# hlk-7688A-kit-v2_2.net
KiCad netlist of a schematic drawn in Altium Designer
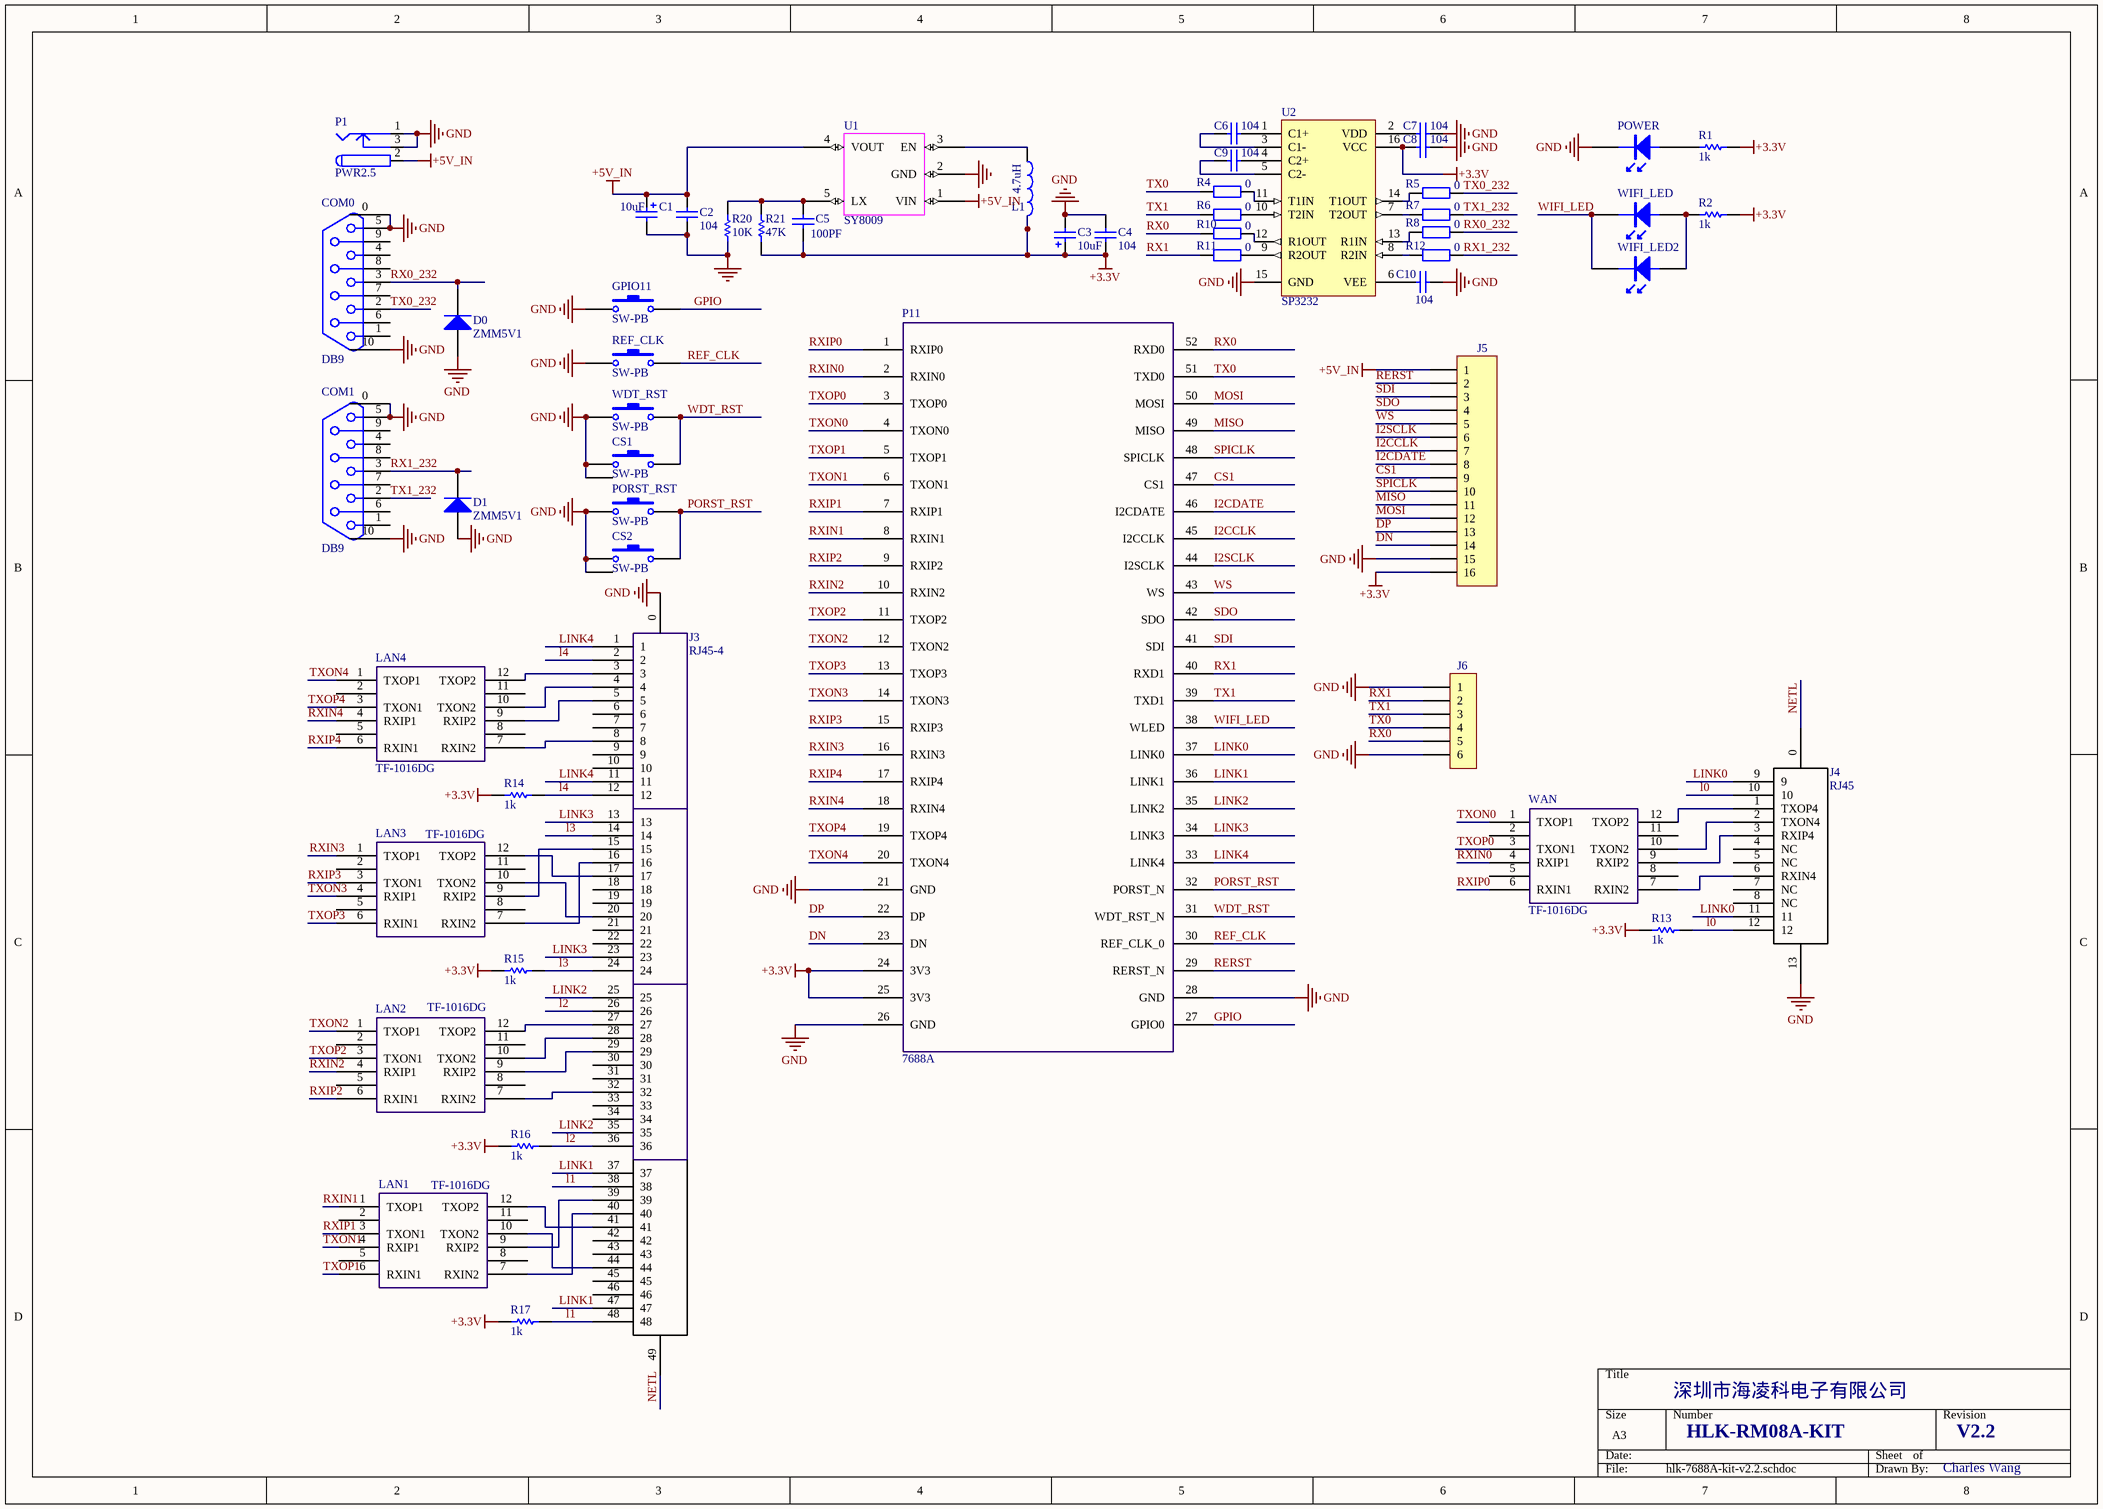
[diagram p0: hlk-7688A-kit-v2.2.schdoc]

(export (version "E")
  (design (tool "Eeschema 10.0.6"))
  (components
    (comp (ref "C1")
      (value "10uF")
      (footprint "0805")
      (description "Polarized Capacitor (Surface Mount)")
      (fields
        (field (name "MANUFACTURER") "Generic Components")
        (field (name "PUBLISHER") "Altium Hobart Technology Centre")
      )
      (libsource (lib "*") (part "Cap Pol3"))
    )
    (comp (ref "C2")
      (value "104")
      (footprint "0603L")
      (description "Capacitor")
      (fields
        (field (name "MANUFACTURER") "Generic Components")
        (field (name "PUBLISHER") "Altium Hobart Technology Centre")
      )
      (libsource (lib "*") (part "Cap"))
    )
    (comp (ref "C3")
      (value "10uF")
      (footprint "0805")
      (description "Polarized Capacitor (Surface Mount)")
      (fields
        (field (name "MANUFACTURER") "Generic Components")
        (field (name "PUBLISHER") "Altium Hobart Technology Centre")
      )
      (libsource (lib "*") (part "Cap Pol3"))
    )
    (comp (ref "C4")
      (value "104")
      (footprint "0603L")
      (description "Capacitor")
      (fields
        (field (name "MANUFACTURER") "Generic Components")
        (field (name "PUBLISHER") "Altium Hobart Technology Centre")
      )
      (libsource (lib "*") (part "Cap"))
    )
    (comp (ref "C5")
      (value "100PF")
      (footprint "0603L")
      (description "Capacitor")
      (fields
        (field (name "MANUFACTURER") "Generic Components")
        (field (name "PUBLISHER") "Altium Hobart Technology Centre")
      )
      (libsource (lib "*") (part "Cap"))
    )
    (comp (ref "C6")
      (value "104")
      (footprint "0603")
      (description "Capacitor")
      (fields (field (name "PUBLISHER") "Altium Limited"))
      (libsource (lib "HLK-RM04_KIT-V2.3") (part "Cap"))
    )
    (comp (ref "C7")
      (value "104")
      (footprint "0603")
      (description "Capacitor")
      (fields (field (name "PUBLISHER") "Altium Limited"))
      (libsource (lib "HLK-RM04_KIT-V2.3") (part "Cap"))
    )
    (comp (ref "C8")
      (value "104")
      (footprint "0603")
      (description "Capacitor")
      (fields (field (name "PUBLISHER") "Altium Limited"))
      (libsource (lib "HLK-RM04_KIT-V2.3") (part "Cap"))
    )
    (comp (ref "C9")
      (value "104")
      (footprint "0603")
      (description "Capacitor")
      (fields (field (name "PUBLISHER") "Altium Limited"))
      (libsource (lib "HLK-RM04_KIT-V2.3") (part "Cap"))
    )
    (comp (ref "C10")
      (value "104")
      (footprint "0603")
      (description "Capacitor")
      (fields (field (name "PUBLISHER") "Altium Limited"))
      (libsource (lib "HLK-RM04_KIT-V2.3") (part "Cap"))
    )
    (comp (ref "COM0") (value "DB9") (footprint "DB9s") (libsource (lib "Schlib1") (part "DB9")))
    (comp (ref "COM1") (value "DB9") (footprint "DB9s") (libsource (lib "Schlib1") (part "DB9")))
    (comp (ref "CS1")
      (value "SW-PB")
      (footprint "K5")
      (description "Switch")
      (fields (field (name "PUBLISHER") "Altium Limited"))
      (libsource (lib "Miscellaneous Devices") (part "SW-PB"))
    )
    (comp (ref "CS2")
      (value "SW-PB")
      (footprint "K5")
      (description "Switch")
      (fields (field (name "PUBLISHER") "Altium Limited"))
      (libsource (lib "Miscellaneous Devices") (part "SW-PB"))
    )
    (comp (ref "D0")
      (value "ZMM5V1")
      (footprint "1005D")
      (description "Default Diode")
      (fields (field (name "PUBLISHER") "Altium Limited"))
      (libsource (lib "Miscellaneous Devices") (part "Diode"))
    )
    (comp (ref "D1")
      (value "ZMM5V1")
      (footprint "1005D")
      (description "Default Diode")
      (fields (field (name "PUBLISHER") "Altium Limited"))
      (libsource (lib "Miscellaneous Devices") (part "Diode"))
    )
    (comp (ref "GPIO11")
      (value "SW-PB")
      (footprint "SWITCH")
      (description "Switch")
      (fields (field (name "PUBLISHER") "Altium Limited"))
      (libsource (lib "") (part "SW-PB_1"))
    )
    (comp (ref "J3") (value "RJ45-4") (footprint "RJ45-4-LED") (libsource (lib "Schlib1") (part "RJ45-4")))
    (comp (ref "J4") (value "RJ45") (libsource (lib "Schlib1") (part "RJ45_1")))
    (comp (ref "J5")
      (value "2.54*16")
      (footprint "HDR1X16")
      (description "Connector")
      (libsource (lib "Miscellaneous Devices") (part "CON16"))
    )
    (comp (ref "J6")
      (value "2.54*6")
      (description "Connector")
      (libsource (lib "Miscellaneous Devices") (part "CON6"))
    )
    (comp (ref "L1") (value "4.7uH") (footprint "L322520") (libsource (lib "ARM9") (part "INDUCTOR1")))
    (comp (ref "LAN1")
      (value "TF-1016DG")
      (footprint "tf-1016dg")
      (libsource (lib "TF-1016DG") (part "Component_1"))
    )
    (comp (ref "LAN2")
      (value "TF-1016DG")
      (footprint "tf-1016dg")
      (libsource (lib "TF-1016DG") (part "Component_1"))
    )
    (comp (ref "LAN3")
      (value "TF-1016DG")
      (footprint "tf-1016dg")
      (libsource (lib "TF-1016DG") (part "Component_1"))
    )
    (comp (ref "LAN4")
      (value "TF-1016DG")
      (footprint "tf-1016dg")
      (libsource (lib "TF-1016DG") (part "Component_1"))
    )
    (comp (ref "P1")
      (value "PWR2.5")
      (footprint "HLK-M35-KIT-V2.1:POWER_STK1")
      (description "Low Voltage Power Supply Connector")
      (libsource (lib "HLK-RM04_KIT-V2.3") (part "PWR2.5"))
    )
    (comp (ref "P11")
      (value "7688A")
      (footprint "7688A:RM08K_52pin")
      (libsource (lib "7688A") (part "Component_1"))
    )
    (comp (ref "PORST_RST")
      (value "SW-PB")
      (footprint "SWITCH")
      (description "Switch")
      (fields (field (name "PUBLISHER") "Altium Limited"))
      (libsource (lib "") (part "SW-PB_1"))
    )
    (comp (ref "POWER")
      (value "~")
      (footprint "0603LED")
      (libsource (lib "Miscellaneous Devices") (part "LED"))
    )
    (comp (ref "R1")
      (value "1k")
      (footprint "0603")
      (description "Resistor")
      (fields (field (name "Comment") "Res1") (field (name "PUBLISHER") "Altium Limited"))
      (libsource (lib "Miscellaneous Devices") (part "Res1"))
    )
    (comp (ref "R2")
      (value "1k")
      (footprint "0603")
      (description "Resistor")
      (fields (field (name "Comment") "Res1") (field (name "PUBLISHER") "Altium Limited"))
      (libsource (lib "Miscellaneous Devices") (part "Res1"))
    )
    (comp (ref "R4")
      (value "0")
      (footprint "0603")
      (description "Resistor")
      (fields (field (name "PUBLISHER") "Altium Limited"))
      (libsource (lib "HLK-RM04_KIT-V2.3") (part "Res2"))
    )
    (comp (ref "R5")
      (value "0")
      (footprint "0603")
      (description "Resistor")
      (fields (field (name "PUBLISHER") "Altium Limited"))
      (libsource (lib "HLK-RM04_KIT-V2.3") (part "Res2"))
    )
    (comp (ref "R6")
      (value "0")
      (footprint "0603")
      (description "Resistor")
      (fields (field (name "PUBLISHER") "Altium Limited"))
      (libsource (lib "HLK-RM04_KIT-V2.3") (part "Res2"))
    )
    (comp (ref "R7")
      (value "0")
      (footprint "0603")
      (description "Resistor")
      (fields (field (name "PUBLISHER") "Altium Limited"))
      (libsource (lib "HLK-RM04_KIT-V2.3") (part "Res2"))
    )
    (comp (ref "R8")
      (value "0")
      (footprint "0603")
      (description "Resistor")
      (fields (field (name "PUBLISHER") "Altium Limited"))
      (libsource (lib "HLK-RM04_KIT-V2.3") (part "Res2"))
    )
    (comp (ref "R10")
      (value "0")
      (footprint "0603")
      (description "Resistor")
      (fields (field (name "PUBLISHER") "Altium Limited"))
      (libsource (lib "HLK-RM04_KIT-V2.3") (part "Res2"))
    )
    (comp (ref "R11")
      (value "0")
      (footprint "0603")
      (description "Resistor")
      (fields (field (name "PUBLISHER") "Altium Limited"))
      (libsource (lib "HLK-RM04_KIT-V2.3") (part "Res2"))
    )
    (comp (ref "R12")
      (value "0")
      (footprint "0603")
      (description "Resistor")
      (fields (field (name "PUBLISHER") "Altium Limited"))
      (libsource (lib "HLK-RM04_KIT-V2.3") (part "Res2"))
    )
    (comp (ref "R13")
      (value "1k")
      (footprint "0603")
      (description "Resistor")
      (fields (field (name "Comment") "Res1") (field (name "PUBLISHER") "Altium Limited"))
      (libsource (lib "Miscellaneous Devices") (part "Res1"))
    )
    (comp (ref "R14")
      (value "1k")
      (footprint "0603")
      (description "Resistor")
      (fields (field (name "Comment") "Res1") (field (name "PUBLISHER") "Altium Limited"))
      (libsource (lib "Miscellaneous Devices") (part "Res1"))
    )
    (comp (ref "R15")
      (value "1k")
      (footprint "0603")
      (description "Resistor")
      (fields (field (name "Comment") "Res1") (field (name "PUBLISHER") "Altium Limited"))
      (libsource (lib "Miscellaneous Devices") (part "Res1"))
    )
    (comp (ref "R16")
      (value "1k")
      (footprint "0603")
      (description "Resistor")
      (fields (field (name "Comment") "Res1") (field (name "PUBLISHER") "Altium Limited"))
      (libsource (lib "Miscellaneous Devices") (part "Res1"))
    )
    (comp (ref "R17")
      (value "1k")
      (footprint "0603")
      (description "Resistor")
      (fields (field (name "Comment") "Res1") (field (name "PUBLISHER") "Altium Limited"))
      (libsource (lib "Miscellaneous Devices") (part "Res1"))
    )
    (comp (ref "R20")
      (value "10K")
      (footprint "0603L")
      (description "Resistor")
      (fields (field (name "Comment") "Res1") (field (name "PUBLISHER") "Altium Limited"))
      (libsource (lib "Miscellaneous Devices") (part "Res1"))
    )
    (comp (ref "R21")
      (value "47K")
      (footprint "0603L")
      (description "Resistor")
      (fields (field (name "Comment") "Res1") (field (name "PUBLISHER") "Altium Limited"))
      (libsource (lib "Miscellaneous Devices") (part "Res1"))
    )
    (comp (ref "REF_CLK")
      (value "SW-PB")
      (footprint "SWITCH")
      (description "Switch")
      (fields (field (name "PUBLISHER") "Altium Limited"))
      (libsource (lib "") (part "SW-PB_1"))
    )
    (comp (ref "U1") (value "SY8009") (footprint "SOT-25") (libsource (lib "ARM9") (part "RT8009")))
    (comp (ref "U2")
      (value "SP3232")
      (footprint "HLK-M35-KIT-V2.1:MAX3232")
      (description "+5V Powered, Multi-Channel RS-232 Driver/Receiver")
      (fields (field (name "PUBLISHER") "Altium Limited"))
      (libsource (lib "HLK-RM04_KIT-V2.3") (part "MAX232ACPE"))
    )
    (comp (ref "WAN")
      (value "TF-1016DG")
      (footprint "tf-1016dg")
      (libsource (lib "TF-1016DG") (part "Component_1"))
    )
    (comp (ref "WDT_RST")
      (value "SW-PB")
      (footprint "SWITCH")
      (description "Switch")
      (fields (field (name "PUBLISHER") "Altium Limited"))
      (libsource (lib "") (part "SW-PB_1"))
    )
    (comp (ref "WIFI_LED")
      (value "~")
      (footprint "0603LED")
      (libsource (lib "Miscellaneous Devices") (part "LED"))
    )
    (comp (ref "WIFI_LED2")
      (value "~")
      (footprint "LED0.2")
      (libsource (lib "Miscellaneous Devices") (part "LED"))
    )
  )
  (nets
    (net (code "1") (name "+3.3V") (class "Default")
      (node (ref "C3") (pin "1") (pinfunction "1_1") (pintype "passive"))
      (node (ref "C4") (pin "1") (pinfunction "1_1") (pintype "passive"))
      (node (ref "C5") (pin "1") (pinfunction "1_1") (pintype "passive"))
      (node (ref "C8") (pin "1") (pinfunction "1_1") (pintype "passive"))
      (node (ref "J5") (pin "16") (pinfunction "16_16") (pintype "passive"))
      (node (ref "L1") (pin "2") (pinfunction "2_2") (pintype "passive"))
      (node (ref "P11") (pin "24") (pinfunction "3V3_24") (pintype "passive"))
      (node (ref "P11") (pin "25") (pinfunction "3V3_25") (pintype "passive"))
      (node (ref "R1") (pin "2") (pinfunction "2_2") (pintype "passive"))
      (node (ref "R13") (pin "2") (pinfunction "2_2") (pintype "passive"))
      (node (ref "R14") (pin "2") (pinfunction "2_2") (pintype "passive"))
      (node (ref "R15") (pin "2") (pinfunction "2_2") (pintype "passive"))
      (node (ref "R16") (pin "2") (pinfunction "2_2") (pintype "passive"))
      (node (ref "R17") (pin "2") (pinfunction "2_2") (pintype "passive"))
      (node (ref "R2") (pin "2") (pinfunction "2_2") (pintype "passive"))
      (node (ref "R21") (pin "2") (pinfunction "2_2") (pintype "passive"))
      (node (ref "U2") (pin "16") (pinfunction "VCC_16") (pintype "power_in"))
    )
    (net (code "2") (name "+5V_IN") (class "Default")
      (node (ref "C1") (pin "1") (pinfunction "1_1") (pintype "passive"))
      (node (ref "C2") (pin "1") (pinfunction "1_1") (pintype "passive"))
      (node (ref "J5") (pin "1") (pinfunction "1_1") (pintype "passive"))
      (node (ref "P1") (pin "2") (pinfunction "2_2") (pintype "power_in"))
      (node (ref "U1") (pin "1") (pinfunction "VIN_1") (pintype "bidirectional"))
      (node (ref "U1") (pin "4") (pinfunction "VOUT_4") (pintype "bidirectional"))
    )
    (net (code "3") (name "/CS1") (class "Default")
      (node (ref "J5") (pin "9") (pinfunction "9_9") (pintype "passive"))
      (node (ref "P11") (pin "47") (pinfunction "CS1_47") (pintype "passive"))
    )
    (net (code "4") (name "/DN") (class "Default")
      (node (ref "J5") (pin "14") (pinfunction "14_14") (pintype "passive"))
      (node (ref "P11") (pin "23") (pinfunction "DN_23") (pintype "passive"))
    )
    (net (code "5") (name "/DP") (class "Default")
      (node (ref "J5") (pin "13") (pinfunction "13_13") (pintype "passive"))
      (node (ref "P11") (pin "22") (pinfunction "DP_22") (pintype "passive"))
    )
    (net (code "6") (name "/GPIO") (class "Default")
      (node (ref "GPIO11") (pin "2") (pinfunction "2_2") (pintype "passive"))
      (node (ref "P11") (pin "27") (pinfunction "GPIO0_27") (pintype "passive"))
    )
    (net (code "7") (name "/I2CCLK") (class "Default")
      (node (ref "J5") (pin "7") (pinfunction "7_7") (pintype "passive"))
      (node (ref "P11") (pin "45") (pinfunction "I2CCLK_45") (pintype "passive"))
    )
    (net (code "8") (name "/I2CDATE") (class "Default")
      (node (ref "J5") (pin "8") (pinfunction "8_8") (pintype "passive"))
      (node (ref "P11") (pin "46") (pinfunction "I2CDATE_46") (pintype "passive"))
    )
    (net (code "9") (name "/I2SCLK") (class "Default")
      (node (ref "J5") (pin "6") (pinfunction "6_6") (pintype "passive"))
      (node (ref "P11") (pin "44") (pinfunction "I2SCLK_44") (pintype "passive"))
    )
    (net (code "10") (name "/LINK0") (class "Default")
      (node (ref "J4") (pin "11") (pinfunction "11_11") (pintype "passive"))
      (node (ref "J4") (pin "9") (pinfunction "9_9") (pintype "passive"))
      (node (ref "P11") (pin "37") (pinfunction "LINK0_37") (pintype "passive"))
    )
    (net (code "11") (name "/LINK1") (class "Default")
      (node (ref "J3") (pin "37") (pinfunction "37_37") (pintype "passive"))
      (node (ref "J3") (pin "47") (pinfunction "47_47") (pintype "passive"))
      (node (ref "P11") (pin "36") (pinfunction "LINK1_36") (pintype "passive"))
    )
    (net (code "12") (name "/LINK2") (class "Default")
      (node (ref "J3") (pin "25") (pinfunction "25_25") (pintype "passive"))
      (node (ref "J3") (pin "35") (pinfunction "35_35") (pintype "passive"))
      (node (ref "P11") (pin "35") (pinfunction "LINK2_35") (pintype "passive"))
    )
    (net (code "13") (name "/LINK3") (class "Default")
      (node (ref "J3") (pin "13") (pinfunction "13_13") (pintype "passive"))
      (node (ref "J3") (pin "23") (pinfunction "23_23") (pintype "passive"))
      (node (ref "P11") (pin "34") (pinfunction "LINK3_34") (pintype "passive"))
    )
    (net (code "14") (name "/LINK4") (class "Default")
      (node (ref "J3") (pin "1") (pinfunction "1_1") (pintype "passive"))
      (node (ref "J3") (pin "11") (pinfunction "11_11") (pintype "passive"))
      (node (ref "P11") (pin "33") (pinfunction "LINK4_33") (pintype "passive"))
    )
    (net (code "15") (name "/MISO") (class "Default")
      (node (ref "J5") (pin "11") (pinfunction "11_11") (pintype "passive"))
      (node (ref "P11") (pin "49") (pinfunction "MISO_49") (pintype "passive"))
    )
    (net (code "16") (name "/MOSI") (class "Default")
      (node (ref "J5") (pin "12") (pinfunction "12_12") (pintype "passive"))
      (node (ref "P11") (pin "50") (pinfunction "MOSI_50") (pintype "passive"))
    )
    (net (code "17") (name "/NETL") (class "Default")
      (node (ref "J3") (pin "49") (pinfunction "49_49") (pintype "passive"))
      (node (ref "J4") (pin "0") (pinfunction "0_0") (pintype "passive"))
    )
    (net (code "18") (name "/PORST_RST") (class "Default")
      (node (ref "CS2") (pin "2") (pinfunction "2_2") (pintype "passive"))
      (node (ref "P11") (pin "32") (pinfunction "PORST_N_32") (pintype "passive"))
      (node (ref "PORST_RST") (pin "2") (pinfunction "2_2") (pintype "passive"))
    )
    (net (code "19") (name "/REF_CLK") (class "Default")
      (node (ref "P11") (pin "30") (pinfunction "REF_CLK_0_30") (pintype "passive"))
      (node (ref "REF_CLK") (pin "2") (pinfunction "2_2") (pintype "passive"))
    )
    (net (code "20") (name "/RERST") (class "Default")
      (node (ref "J5") (pin "2") (pinfunction "2_2") (pintype "passive"))
      (node (ref "P11") (pin "29") (pinfunction "RERST_N_29") (pintype "passive"))
    )
    (net (code "21") (name "/RX0") (class "Default")
      (node (ref "J6") (pin "5") (pinfunction "5_5") (pintype "passive"))
      (node (ref "P11") (pin "52") (pinfunction "RXD0_52") (pintype "passive"))
      (node (ref "R10") (pin "1") (pinfunction "1_1") (pintype "passive"))
    )
    (net (code "22") (name "/RX0_232") (class "Default")
      (node (ref "COM0") (pin "3") (pinfunction "3_3") (pintype "passive"))
      (node (ref "D0") (pin "2") (pinfunction "K_2") (pintype "passive"))
      (node (ref "R8") (pin "2") (pinfunction "2_2") (pintype "passive"))
    )
    (net (code "23") (name "/RX1") (class "Default")
      (node (ref "J6") (pin "2") (pinfunction "2_2") (pintype "passive"))
      (node (ref "P11") (pin "40") (pinfunction "RXD1_40") (pintype "passive"))
      (node (ref "R11") (pin "1") (pinfunction "1_1") (pintype "passive"))
    )
    (net (code "24") (name "/RX1_232") (class "Default")
      (node (ref "COM1") (pin "3") (pinfunction "3_3") (pintype "passive"))
      (node (ref "D1") (pin "2") (pinfunction "K_2") (pintype "passive"))
      (node (ref "R12") (pin "2") (pinfunction "2_2") (pintype "passive"))
    )
    (net (code "25") (name "/RXIN0") (class "Default")
      (node (ref "P11") (pin "2") (pinfunction "RXIN0_2") (pintype "passive"))
      (node (ref "WAN") (pin "4") (pinfunction "RXIP1_4") (pintype "passive"))
    )
    (net (code "26") (name "/RXIN1") (class "Default")
      (node (ref "LAN1") (pin "1") (pinfunction "TXOP1_1") (pintype "passive"))
      (node (ref "P11") (pin "8") (pinfunction "RXIN1_8") (pintype "passive"))
    )
    (net (code "27") (name "/RXIN2") (class "Default")
      (node (ref "LAN2") (pin "4") (pinfunction "RXIP1_4") (pintype "passive"))
      (node (ref "P11") (pin "10") (pinfunction "RXIN2_10") (pintype "passive"))
    )
    (net (code "28") (name "/RXIN3") (class "Default")
      (node (ref "LAN3") (pin "1") (pinfunction "TXOP1_1") (pintype "passive"))
      (node (ref "P11") (pin "16") (pinfunction "RXIN3_16") (pintype "passive"))
    )
    (net (code "29") (name "/RXIN4") (class "Default")
      (node (ref "LAN4") (pin "4") (pinfunction "RXIP1_4") (pintype "passive"))
      (node (ref "P11") (pin "18") (pinfunction "RXIN4_18") (pintype "passive"))
    )
    (net (code "30") (name "/RXIP0") (class "Default")
      (node (ref "P11") (pin "1") (pinfunction "RXIP0_1") (pintype "passive"))
      (node (ref "WAN") (pin "6") (pinfunction "RXIN1_6") (pintype "passive"))
    )
    (net (code "31") (name "/RXIP1") (class "Default")
      (node (ref "LAN1") (pin "3") (pinfunction "TXON1_3") (pintype "passive"))
      (node (ref "P11") (pin "7") (pinfunction "RXIP1_7") (pintype "passive"))
    )
    (net (code "32") (name "/RXIP2") (class "Default")
      (node (ref "LAN2") (pin "6") (pinfunction "RXIN1_6") (pintype "passive"))
      (node (ref "P11") (pin "9") (pinfunction "RXIP2_9") (pintype "passive"))
    )
    (net (code "33") (name "/RXIP3") (class "Default")
      (node (ref "LAN3") (pin "3") (pinfunction "TXON1_3") (pintype "passive"))
      (node (ref "P11") (pin "15") (pinfunction "RXIP3_15") (pintype "passive"))
    )
    (net (code "34") (name "/RXIP4") (class "Default")
      (node (ref "LAN4") (pin "6") (pinfunction "RXIN1_6") (pintype "passive"))
      (node (ref "P11") (pin "17") (pinfunction "RXIP4_17") (pintype "passive"))
    )
    (net (code "35") (name "/SDI") (class "Default")
      (node (ref "J5") (pin "3") (pinfunction "3_3") (pintype "passive"))
      (node (ref "P11") (pin "41") (pinfunction "SDI_41") (pintype "passive"))
    )
    (net (code "36") (name "/SDO") (class "Default")
      (node (ref "J5") (pin "4") (pinfunction "4_4") (pintype "passive"))
      (node (ref "P11") (pin "42") (pinfunction "SDO_42") (pintype "passive"))
    )
    (net (code "37") (name "/SPICLK") (class "Default")
      (node (ref "J5") (pin "10") (pinfunction "10_10") (pintype "passive"))
      (node (ref "P11") (pin "48") (pinfunction "SPICLK_48") (pintype "passive"))
    )
    (net (code "38") (name "/TX0") (class "Default")
      (node (ref "J6") (pin "4") (pinfunction "4_4") (pintype "passive"))
      (node (ref "P11") (pin "51") (pinfunction "TXD0_51") (pintype "passive"))
      (node (ref "R4") (pin "1") (pinfunction "1_1") (pintype "passive"))
    )
    (net (code "39") (name "/TX0_232") (class "Default")
      (node (ref "COM0") (pin "2") (pinfunction "2_2") (pintype "passive"))
      (node (ref "R5") (pin "2") (pinfunction "2_2") (pintype "passive"))
    )
    (net (code "40") (name "/TX1") (class "Default")
      (node (ref "J6") (pin "3") (pinfunction "3_3") (pintype "passive"))
      (node (ref "P11") (pin "39") (pinfunction "TXD1_39") (pintype "passive"))
      (node (ref "R6") (pin "1") (pinfunction "1_1") (pintype "passive"))
    )
    (net (code "41") (name "/TX1_232") (class "Default")
      (node (ref "COM1") (pin "2") (pinfunction "2_2") (pintype "passive"))
      (node (ref "R7") (pin "2") (pinfunction "2_2") (pintype "passive"))
    )
    (net (code "42") (name "/TXON0") (class "Default")
      (node (ref "P11") (pin "4") (pinfunction "TXON0_4") (pintype "passive"))
      (node (ref "WAN") (pin "1") (pinfunction "TXOP1_1") (pintype "passive"))
    )
    (net (code "43") (name "/TXON1") (class "Default")
      (node (ref "LAN1") (pin "4") (pinfunction "RXIP1_4") (pintype "passive"))
      (node (ref "P11") (pin "6") (pinfunction "TXON1_6") (pintype "passive"))
    )
    (net (code "44") (name "/TXON2") (class "Default")
      (node (ref "LAN2") (pin "1") (pinfunction "TXOP1_1") (pintype "passive"))
      (node (ref "P11") (pin "12") (pinfunction "TXON2_12") (pintype "passive"))
    )
    (net (code "45") (name "/TXON3") (class "Default")
      (node (ref "LAN3") (pin "4") (pinfunction "RXIP1_4") (pintype "passive"))
      (node (ref "P11") (pin "14") (pinfunction "TXON3_14") (pintype "passive"))
    )
    (net (code "46") (name "/TXON4") (class "Default")
      (node (ref "LAN4") (pin "1") (pinfunction "TXOP1_1") (pintype "passive"))
      (node (ref "P11") (pin "20") (pinfunction "TXON4_20") (pintype "passive"))
    )
    (net (code "47") (name "/TXOP0") (class "Default")
      (node (ref "P11") (pin "3") (pinfunction "TXOP0_3") (pintype "passive"))
      (node (ref "WAN") (pin "3") (pinfunction "TXON1_3") (pintype "passive"))
    )
    (net (code "48") (name "/TXOP1") (class "Default")
      (node (ref "LAN1") (pin "6") (pinfunction "RXIN1_6") (pintype "passive"))
      (node (ref "P11") (pin "5") (pinfunction "TXOP1_5") (pintype "passive"))
    )
    (net (code "49") (name "/TXOP2") (class "Default")
      (node (ref "LAN2") (pin "3") (pinfunction "TXON1_3") (pintype "passive"))
      (node (ref "P11") (pin "11") (pinfunction "TXOP2_11") (pintype "passive"))
    )
    (net (code "50") (name "/TXOP3") (class "Default")
      (node (ref "LAN3") (pin "6") (pinfunction "RXIN1_6") (pintype "passive"))
      (node (ref "P11") (pin "13") (pinfunction "TXOP3_13") (pintype "passive"))
    )
    (net (code "51") (name "/TXOP4") (class "Default")
      (node (ref "LAN4") (pin "3") (pinfunction "TXON1_3") (pintype "passive"))
      (node (ref "P11") (pin "19") (pinfunction "TXOP4_19") (pintype "passive"))
    )
    (net (code "52") (name "/WDT_RST") (class "Default")
      (node (ref "CS1") (pin "2") (pinfunction "2_2") (pintype "passive"))
      (node (ref "P11") (pin "31") (pinfunction "WDT_RST_N_31") (pintype "passive"))
      (node (ref "WDT_RST") (pin "2") (pinfunction "2_2") (pintype "passive"))
    )
    (net (code "53") (name "/WIFI_LED") (class "Default")
      (node (ref "P11") (pin "38") (pinfunction "WLED_38") (pintype "passive"))
      (node (ref "WIFI_LED") (pin "2") (pinfunction "2_2") (pintype "passive"))
      (node (ref "WIFI_LED2") (pin "2") (pinfunction "2_2") (pintype "passive"))
    )
    (net (code "54") (name "/WS") (class "Default")
      (node (ref "J5") (pin "5") (pinfunction "5_5") (pintype "passive"))
      (node (ref "P11") (pin "43") (pinfunction "WS_43") (pintype "passive"))
    )
    (net (code "55") (name "/l0") (class "Default")
      (node (ref "J4") (pin "10") (pinfunction "10_10") (pintype "passive"))
      (node (ref "J4") (pin "12") (pinfunction "12_12") (pintype "passive"))
      (node (ref "R13") (pin "1") (pinfunction "1_1") (pintype "passive"))
    )
    (net (code "56") (name "/l1") (class "Default")
      (node (ref "J3") (pin "38") (pinfunction "38_38") (pintype "passive"))
      (node (ref "J3") (pin "48") (pinfunction "48_48") (pintype "passive"))
      (node (ref "R17") (pin "1") (pinfunction "1_1") (pintype "passive"))
    )
    (net (code "57") (name "/l2") (class "Default")
      (node (ref "J3") (pin "26") (pinfunction "26_26") (pintype "passive"))
      (node (ref "J3") (pin "36") (pinfunction "36_36") (pintype "passive"))
      (node (ref "R16") (pin "1") (pinfunction "1_1") (pintype "passive"))
    )
    (net (code "58") (name "/l3") (class "Default")
      (node (ref "J3") (pin "14") (pinfunction "14_14") (pintype "passive"))
      (node (ref "J3") (pin "24") (pinfunction "24_24") (pintype "passive"))
      (node (ref "R15") (pin "1") (pinfunction "1_1") (pintype "passive"))
    )
    (net (code "59") (name "/l4") (class "Default")
      (node (ref "J3") (pin "12") (pinfunction "12_12") (pintype "passive"))
      (node (ref "J3") (pin "2") (pinfunction "2_2") (pintype "passive"))
      (node (ref "R14") (pin "1") (pinfunction "1_1") (pintype "passive"))
    )
    (net (code "60") (name "GND") (class "Default")
      (node (ref "C1") (pin "2") (pinfunction "2_2") (pintype "passive"))
      (node (ref "C10") (pin "1") (pinfunction "1_1") (pintype "passive"))
      (node (ref "C2") (pin "2") (pinfunction "2_2") (pintype "passive"))
      (node (ref "C3") (pin "2") (pinfunction "2_2") (pintype "passive"))
      (node (ref "C4") (pin "2") (pinfunction "2_2") (pintype "passive"))
      (node (ref "C7") (pin "2") (pinfunction "2_2") (pintype "passive"))
      (node (ref "C8") (pin "2") (pinfunction "2_2") (pintype "passive"))
      (node (ref "COM0") (pin "0") (pinfunction "0_0") (pintype "passive"))
      (node (ref "COM0") (pin "10") (pinfunction "10_10") (pintype "passive"))
      (node (ref "COM0") (pin "5") (pinfunction "5_5") (pintype "passive"))
      (node (ref "COM1") (pin "0") (pinfunction "0_0") (pintype "passive"))
      (node (ref "COM1") (pin "10") (pinfunction "10_10") (pintype "passive"))
      (node (ref "COM1") (pin "5") (pinfunction "5_5") (pintype "passive"))
      (node (ref "CS1") (pin "1") (pinfunction "1_1") (pintype "passive"))
      (node (ref "CS1") (pin "3") (pintype "passive"))
      (node (ref "CS2") (pin "1") (pinfunction "1_1") (pintype "passive"))
      (node (ref "CS2") (pin "3") (pintype "passive"))
      (node (ref "D0") (pin "1") (pinfunction "A_1") (pintype "passive"))
      (node (ref "D1") (pin "1") (pinfunction "A_1") (pintype "passive"))
      (node (ref "GPIO11") (pin "1") (pinfunction "1_1") (pintype "passive"))
      (node (ref "J3") (pin "0") (pinfunction "0_0") (pintype "passive"))
      (node (ref "J4") (pin "13") (pinfunction "13_13") (pintype "passive"))
      (node (ref "J5") (pin "15") (pinfunction "15_15") (pintype "passive"))
      (node (ref "J6") (pin "1") (pinfunction "1_1") (pintype "passive"))
      (node (ref "J6") (pin "6") (pinfunction "6_6") (pintype "passive"))
      (node (ref "P1") (pin "1") (pinfunction "1_1") (pintype "power_in"))
      (node (ref "P1") (pin "3") (pinfunction "3_3") (pintype "power_in"))
      (node (ref "P11") (pin "21") (pinfunction "GND_21") (pintype "passive"))
      (node (ref "P11") (pin "26") (pinfunction "GND_26") (pintype "passive"))
      (node (ref "P11") (pin "28") (pinfunction "GND_28") (pintype "passive"))
      (node (ref "PORST_RST") (pin "1") (pinfunction "1_1") (pintype "passive"))
      (node (ref "POWER") (pin "2") (pinfunction "2_2") (pintype "passive"))
      (node (ref "R20") (pin "1") (pinfunction "1_1") (pintype "passive"))
      (node (ref "REF_CLK") (pin "1") (pinfunction "1_1") (pintype "passive"))
      (node (ref "U1") (pin "2") (pinfunction "GND_2") (pintype "bidirectional"))
      (node (ref "U2") (pin "15") (pinfunction "GND_15") (pintype "power_in"))
      (node (ref "WDT_RST") (pin "1") (pinfunction "1_1") (pintype "passive"))
    )
    (net (code "61") (name "Net-(J4-RXIN4)") (class "Default")
      (node (ref "J4") (pin "6") (pinfunction "RXIN4_6") (pintype "passive"))
      (node (ref "WAN") (pin "7") (pinfunction "RXIN2_7") (pintype "passive"))
    )
    (net (code "62") (name "Net-(J4-RXIP4)") (class "Default")
      (node (ref "J4") (pin "3") (pinfunction "RXIP4_3") (pintype "passive"))
      (node (ref "WAN") (pin "9") (pinfunction "RXIP2_9") (pintype "passive"))
    )
    (net (code "63") (name "Net-(J4-TXON4)") (class "Default")
      (node (ref "J4") (pin "2") (pinfunction "TXON4_2") (pintype "passive"))
      (node (ref "WAN") (pin "10") (pinfunction "TXON2_10") (pintype "passive"))
    )
    (net (code "64") (name "Net-(J4-TXOP4)") (class "Default")
      (node (ref "J4") (pin "1") (pinfunction "TXOP4_1") (pintype "passive"))
      (node (ref "WAN") (pin "12") (pinfunction "TXOP2_12") (pintype "passive"))
    )
    (net (code "65") (name "Net-(LAN1-RXIN2)") (class "Default")
      (node (ref "J3") (pin "40") (pinfunction "40_40") (pintype "passive"))
      (node (ref "LAN1") (pin "7") (pinfunction "RXIN2_7") (pintype "passive"))
    )
    (net (code "66") (name "Net-(LAN1-RXIP2)") (class "Default")
      (node (ref "J3") (pin "39") (pinfunction "39_39") (pintype "passive"))
      (node (ref "LAN1") (pin "9") (pinfunction "RXIP2_9") (pintype "passive"))
    )
    (net (code "67") (name "Net-(LAN1-TXON2)") (class "Default")
      (node (ref "J3") (pin "44") (pinfunction "44_44") (pintype "passive"))
      (node (ref "LAN1") (pin "10") (pinfunction "TXON2_10") (pintype "passive"))
    )
    (net (code "68") (name "Net-(LAN1-TXOP2)") (class "Default")
      (node (ref "J3") (pin "41") (pinfunction "41_41") (pintype "passive"))
      (node (ref "LAN1") (pin "12") (pinfunction "TXOP2_12") (pintype "passive"))
    )
    (net (code "69") (name "Net-(LAN2-RXIN2)") (class "Default")
      (node (ref "J3") (pin "32") (pinfunction "32_32") (pintype "passive"))
      (node (ref "LAN2") (pin "7") (pinfunction "RXIN2_7") (pintype "passive"))
    )
    (net (code "70") (name "Net-(LAN2-RXIP2)") (class "Default")
      (node (ref "J3") (pin "29") (pinfunction "29_29") (pintype "passive"))
      (node (ref "LAN2") (pin "9") (pinfunction "RXIP2_9") (pintype "passive"))
    )
    (net (code "71") (name "Net-(LAN2-TXON2)") (class "Default")
      (node (ref "J3") (pin "28") (pinfunction "28_28") (pintype "passive"))
      (node (ref "LAN2") (pin "10") (pinfunction "TXON2_10") (pintype "passive"))
    )
    (net (code "72") (name "Net-(LAN2-TXOP2)") (class "Default")
      (node (ref "J3") (pin "27") (pinfunction "27_27") (pintype "passive"))
      (node (ref "LAN2") (pin "12") (pinfunction "TXOP2_12") (pintype "passive"))
    )
    (net (code "73") (name "Net-(LAN3-RXIN2)") (class "Default")
      (node (ref "J3") (pin "16") (pinfunction "16_16") (pintype "passive"))
      (node (ref "LAN3") (pin "7") (pinfunction "RXIN2_7") (pintype "passive"))
    )
    (net (code "74") (name "Net-(LAN3-RXIP2)") (class "Default")
      (node (ref "J3") (pin "15") (pinfunction "15_15") (pintype "passive"))
      (node (ref "LAN3") (pin "9") (pinfunction "RXIP2_9") (pintype "passive"))
    )
    (net (code "75") (name "Net-(LAN3-TXON2)") (class "Default")
      (node (ref "J3") (pin "20") (pinfunction "20_20") (pintype "passive"))
      (node (ref "LAN3") (pin "10") (pinfunction "TXON2_10") (pintype "passive"))
    )
    (net (code "76") (name "Net-(LAN3-TXOP2)") (class "Default")
      (node (ref "J3") (pin "17") (pinfunction "17_17") (pintype "passive"))
      (node (ref "LAN3") (pin "12") (pinfunction "TXOP2_12") (pintype "passive"))
    )
    (net (code "77") (name "Net-(LAN4-RXIN2)") (class "Default")
      (node (ref "J3") (pin "8") (pinfunction "8_8") (pintype "passive"))
      (node (ref "LAN4") (pin "7") (pinfunction "RXIN2_7") (pintype "passive"))
    )
    (net (code "78") (name "Net-(LAN4-RXIP2)") (class "Default")
      (node (ref "J3") (pin "5") (pinfunction "5_5") (pintype "passive"))
      (node (ref "LAN4") (pin "9") (pinfunction "RXIP2_9") (pintype "passive"))
    )
    (net (code "79") (name "Net-(LAN4-TXON2)") (class "Default")
      (node (ref "J3") (pin "4") (pinfunction "4_4") (pintype "passive"))
      (node (ref "LAN4") (pin "10") (pinfunction "TXON2_10") (pintype "passive"))
    )
    (net (code "80") (name "Net-(LAN4-TXOP2)") (class "Default")
      (node (ref "J3") (pin "3") (pinfunction "3_3") (pintype "passive"))
      (node (ref "LAN4") (pin "12") (pinfunction "TXOP2_12") (pintype "passive"))
    )
    (net (code "81") (name "Net-(POWER-Pad1)") (class "Default")
      (node (ref "POWER") (pin "1") (pinfunction "1_1") (pintype "passive"))
      (node (ref "R1") (pin "1") (pinfunction "1_1") (pintype "passive"))
    )
    (net (code "82") (name "Net-(R2-Pad1)") (class "Default")
      (node (ref "R2") (pin "1") (pinfunction "1_1") (pintype "passive"))
      (node (ref "WIFI_LED") (pin "1") (pinfunction "1_1") (pintype "passive"))
      (node (ref "WIFI_LED2") (pin "1") (pinfunction "1_1") (pintype "passive"))
    )
    (net (code "83") (name "Net-(U1-EN)") (class "Default")
      (node (ref "L1") (pin "1") (pinfunction "1_1") (pintype "passive"))
      (node (ref "U1") (pin "3") (pinfunction "EN_3") (pintype "bidirectional"))
    )
    (net (code "84") (name "Net-(U1-LX)") (class "Default")
      (node (ref "C5") (pin "2") (pinfunction "2_2") (pintype "passive"))
      (node (ref "R20") (pin "2") (pinfunction "2_2") (pintype "passive"))
      (node (ref "R21") (pin "1") (pinfunction "1_1") (pintype "passive"))
      (node (ref "U1") (pin "5") (pinfunction "LX_5") (pintype "bidirectional"))
    )
    (net (code "85") (name "Net-(U2-C1+)") (class "Default")
      (node (ref "C6") (pin "2") (pinfunction "2_2") (pintype "passive"))
      (node (ref "U2") (pin "1") (pinfunction "C1+_1") (pintype "passive"))
    )
    (net (code "86") (name "Net-(U2-C1-)") (class "Default")
      (node (ref "C6") (pin "1") (pinfunction "1_1") (pintype "passive"))
      (node (ref "U2") (pin "3") (pinfunction "C1-_3") (pintype "passive"))
    )
    (net (code "87") (name "Net-(U2-C2+)") (class "Default")
      (node (ref "C9") (pin "2") (pinfunction "2_2") (pintype "passive"))
      (node (ref "U2") (pin "4") (pinfunction "C2+_4") (pintype "passive"))
    )
    (net (code "88") (name "Net-(U2-C2-)") (class "Default")
      (node (ref "C9") (pin "1") (pinfunction "1_1") (pintype "passive"))
      (node (ref "U2") (pin "5") (pinfunction "C2-_5") (pintype "passive"))
    )
    (net (code "89") (name "Net-(U2-R1IN)") (class "Default")
      (node (ref "R8") (pin "1") (pinfunction "1_1") (pintype "passive"))
      (node (ref "U2") (pin "13") (pinfunction "R1IN_13") (pintype "input"))
    )
    (net (code "90") (name "Net-(U2-R1OUT)") (class "Default")
      (node (ref "R10") (pin "2") (pinfunction "2_2") (pintype "passive"))
      (node (ref "U2") (pin "12") (pinfunction "R1OUT_12") (pintype "output"))
    )
    (net (code "91") (name "Net-(U2-R2IN)") (class "Default")
      (node (ref "R12") (pin "1") (pinfunction "1_1") (pintype "passive"))
      (node (ref "U2") (pin "8") (pinfunction "R2IN_8") (pintype "input"))
    )
    (net (code "92") (name "Net-(U2-R2OUT)") (class "Default")
      (node (ref "R11") (pin "2") (pinfunction "2_2") (pintype "passive"))
      (node (ref "U2") (pin "9") (pinfunction "R2OUT_9") (pintype "output"))
    )
    (net (code "93") (name "Net-(U2-T1IN)") (class "Default")
      (node (ref "R4") (pin "2") (pinfunction "2_2") (pintype "passive"))
      (node (ref "U2") (pin "11") (pinfunction "T1IN_11") (pintype "input"))
    )
    (net (code "94") (name "Net-(U2-T1OUT)") (class "Default")
      (node (ref "R5") (pin "1") (pinfunction "1_1") (pintype "passive"))
      (node (ref "U2") (pin "14") (pinfunction "T1OUT_14") (pintype "output"))
    )
    (net (code "95") (name "Net-(U2-T2IN)") (class "Default")
      (node (ref "R6") (pin "2") (pinfunction "2_2") (pintype "passive"))
      (node (ref "U2") (pin "10") (pinfunction "T2IN_10") (pintype "input"))
    )
    (net (code "96") (name "Net-(U2-T2OUT)") (class "Default")
      (node (ref "R7") (pin "1") (pinfunction "1_1") (pintype "passive"))
      (node (ref "U2") (pin "7") (pinfunction "T2OUT_7") (pintype "output"))
    )
    (net (code "97") (name "Net-(U2-VDD)") (class "Default")
      (node (ref "C7") (pin "1") (pinfunction "1_1") (pintype "passive"))
      (node (ref "U2") (pin "2") (pinfunction "VDD_2") (pintype "power_in"))
    )
    (net (code "98") (name "Net-(U2-VEE)") (class "Default")
      (node (ref "C10") (pin "2") (pinfunction "2_2") (pintype "passive"))
      (node (ref "U2") (pin "6") (pinfunction "VEE_6") (pintype "power_in"))
    )
    (net (code "99") (name "unconnected-(COM0-Pad1)") (class "Default")
      (node (ref "COM0") (pin "1") (pinfunction "1_1") (pintype "passive"))
    )
    (net (code "100") (name "unconnected-(COM0-Pad4)") (class "Default")
      (node (ref "COM0") (pin "4") (pinfunction "4_4") (pintype "passive"))
    )
    (net (code "101") (name "unconnected-(COM0-Pad6)") (class "Default")
      (node (ref "COM0") (pin "6") (pinfunction "6_6") (pintype "passive"))
    )
    (net (code "102") (name "unconnected-(COM0-Pad7)") (class "Default")
      (node (ref "COM0") (pin "7") (pinfunction "7_7") (pintype "passive"))
    )
    (net (code "103") (name "unconnected-(COM0-Pad8)") (class "Default")
      (node (ref "COM0") (pin "8") (pinfunction "8_8") (pintype "passive"))
    )
    (net (code "104") (name "unconnected-(COM0-Pad9)") (class "Default")
      (node (ref "COM0") (pin "9") (pinfunction "9_9") (pintype "passive"))
    )
    (net (code "105") (name "unconnected-(COM1-Pad1)") (class "Default")
      (node (ref "COM1") (pin "1") (pinfunction "1_1") (pintype "passive"))
    )
    (net (code "106") (name "unconnected-(COM1-Pad4)") (class "Default")
      (node (ref "COM1") (pin "4") (pinfunction "4_4") (pintype "passive"))
    )
    (net (code "107") (name "unconnected-(COM1-Pad6)") (class "Default")
      (node (ref "COM1") (pin "6") (pinfunction "6_6") (pintype "passive"))
    )
    (net (code "108") (name "unconnected-(COM1-Pad7)") (class "Default")
      (node (ref "COM1") (pin "7") (pinfunction "7_7") (pintype "passive"))
    )
    (net (code "109") (name "unconnected-(COM1-Pad8)") (class "Default")
      (node (ref "COM1") (pin "8") (pinfunction "8_8") (pintype "passive"))
    )
    (net (code "110") (name "unconnected-(COM1-Pad9)") (class "Default")
      (node (ref "COM1") (pin "9") (pinfunction "9_9") (pintype "passive"))
    )
    (net (code "111") (name "unconnected-(J3-Pad6)") (class "Default")
      (node (ref "J3") (pin "6") (pinfunction "6_6") (pintype "passive"))
    )
    (net (code "112") (name "unconnected-(J3-Pad7)") (class "Default")
      (node (ref "J3") (pin "7") (pinfunction "7_7") (pintype "passive"))
    )
    (net (code "113") (name "unconnected-(J3-Pad9)") (class "Default")
      (node (ref "J3") (pin "9") (pinfunction "9_9") (pintype "passive"))
    )
    (net (code "114") (name "unconnected-(J3-Pad10)") (class "Default")
      (node (ref "J3") (pin "10") (pinfunction "10_10") (pintype "passive"))
    )
    (net (code "115") (name "unconnected-(J3-Pad18)") (class "Default")
      (node (ref "J3") (pin "18") (pinfunction "18_18") (pintype "passive"))
    )
    (net (code "116") (name "unconnected-(J3-Pad19)") (class "Default")
      (node (ref "J3") (pin "19") (pinfunction "19_19") (pintype "passive"))
    )
    (net (code "117") (name "unconnected-(J3-Pad21)") (class "Default")
      (node (ref "J3") (pin "21") (pinfunction "21_21") (pintype "passive"))
    )
    (net (code "118") (name "unconnected-(J3-Pad22)") (class "Default")
      (node (ref "J3") (pin "22") (pinfunction "22_22") (pintype "passive"))
    )
    (net (code "119") (name "unconnected-(J3-Pad30)") (class "Default")
      (node (ref "J3") (pin "30") (pinfunction "30_30") (pintype "passive"))
    )
    (net (code "120") (name "unconnected-(J3-Pad31)") (class "Default")
      (node (ref "J3") (pin "31") (pinfunction "31_31") (pintype "passive"))
    )
    (net (code "121") (name "unconnected-(J3-Pad33)") (class "Default")
      (node (ref "J3") (pin "33") (pinfunction "33_33") (pintype "passive"))
    )
    (net (code "122") (name "unconnected-(J3-Pad34)") (class "Default")
      (node (ref "J3") (pin "34") (pinfunction "34_34") (pintype "passive"))
    )
    (net (code "123") (name "unconnected-(J3-Pad42)") (class "Default")
      (node (ref "J3") (pin "42") (pinfunction "42_42") (pintype "passive"))
    )
    (net (code "124") (name "unconnected-(J3-Pad43)") (class "Default")
      (node (ref "J3") (pin "43") (pinfunction "43_43") (pintype "passive"))
    )
    (net (code "125") (name "unconnected-(J3-Pad45)") (class "Default")
      (node (ref "J3") (pin "45") (pinfunction "45_45") (pintype "passive"))
    )
    (net (code "126") (name "unconnected-(J3-Pad46)") (class "Default")
      (node (ref "J3") (pin "46") (pinfunction "46_46") (pintype "passive"))
    )
    (net (code "127") (name "unconnected-(J4-NC-Pad4)") (class "Default")
      (node (ref "J4") (pin "4") (pinfunction "NC_4") (pintype "passive"))
    )
    (net (code "128") (name "unconnected-(J4-NC-Pad5)") (class "Default")
      (node (ref "J4") (pin "5") (pinfunction "NC_5") (pintype "passive"))
    )
    (net (code "129") (name "unconnected-(J4-NC-Pad7)") (class "Default")
      (node (ref "J4") (pin "7") (pinfunction "NC_7") (pintype "passive"))
    )
    (net (code "130") (name "unconnected-(J4-NC-Pad8)") (class "Default")
      (node (ref "J4") (pin "8") (pinfunction "NC_8") (pintype "passive"))
    )
    (net (code "131") (name "unconnected-(LAN1-Pad2)") (class "Default")
      (node (ref "LAN1") (pin "2") (pintype "passive"))
    )
    (net (code "132") (name "unconnected-(LAN1-Pad5)") (class "Default")
      (node (ref "LAN1") (pin "5") (pintype "passive"))
    )
    (net (code "133") (name "unconnected-(LAN1-Pad8)") (class "Default")
      (node (ref "LAN1") (pin "8") (pintype "passive"))
    )
    (net (code "134") (name "unconnected-(LAN1-Pad11)") (class "Default")
      (node (ref "LAN1") (pin "11") (pintype "passive"))
    )
    (net (code "135") (name "unconnected-(LAN2-Pad2)") (class "Default")
      (node (ref "LAN2") (pin "2") (pintype "passive"))
    )
    (net (code "136") (name "unconnected-(LAN2-Pad5)") (class "Default")
      (node (ref "LAN2") (pin "5") (pintype "passive"))
    )
    (net (code "137") (name "unconnected-(LAN2-Pad8)") (class "Default")
      (node (ref "LAN2") (pin "8") (pintype "passive"))
    )
    (net (code "138") (name "unconnected-(LAN2-Pad11)") (class "Default")
      (node (ref "LAN2") (pin "11") (pintype "passive"))
    )
    (net (code "139") (name "unconnected-(LAN3-Pad2)") (class "Default")
      (node (ref "LAN3") (pin "2") (pintype "passive"))
    )
    (net (code "140") (name "unconnected-(LAN3-Pad5)") (class "Default")
      (node (ref "LAN3") (pin "5") (pintype "passive"))
    )
    (net (code "141") (name "unconnected-(LAN3-Pad8)") (class "Default")
      (node (ref "LAN3") (pin "8") (pintype "passive"))
    )
    (net (code "142") (name "unconnected-(LAN3-Pad11)") (class "Default")
      (node (ref "LAN3") (pin "11") (pintype "passive"))
    )
    (net (code "143") (name "unconnected-(LAN4-Pad2)") (class "Default")
      (node (ref "LAN4") (pin "2") (pintype "passive"))
    )
    (net (code "144") (name "unconnected-(LAN4-Pad5)") (class "Default")
      (node (ref "LAN4") (pin "5") (pintype "passive"))
    )
    (net (code "145") (name "unconnected-(LAN4-Pad8)") (class "Default")
      (node (ref "LAN4") (pin "8") (pintype "passive"))
    )
    (net (code "146") (name "unconnected-(LAN4-Pad11)") (class "Default")
      (node (ref "LAN4") (pin "11") (pintype "passive"))
    )
    (net (code "147") (name "unconnected-(WAN-Pad2)") (class "Default")
      (node (ref "WAN") (pin "2") (pintype "passive"))
    )
    (net (code "148") (name "unconnected-(WAN-Pad5)") (class "Default")
      (node (ref "WAN") (pin "5") (pintype "passive"))
    )
    (net (code "149") (name "unconnected-(WAN-Pad8)") (class "Default")
      (node (ref "WAN") (pin "8") (pintype "passive"))
    )
    (net (code "150") (name "unconnected-(WAN-Pad11)") (class "Default")
      (node (ref "WAN") (pin "11") (pintype "passive"))
    )
  )
)
